# 1-Schematic_R4_Odzyskowa_Dolna.net
KiCad netlist of a schematic drawn in EasyEDA
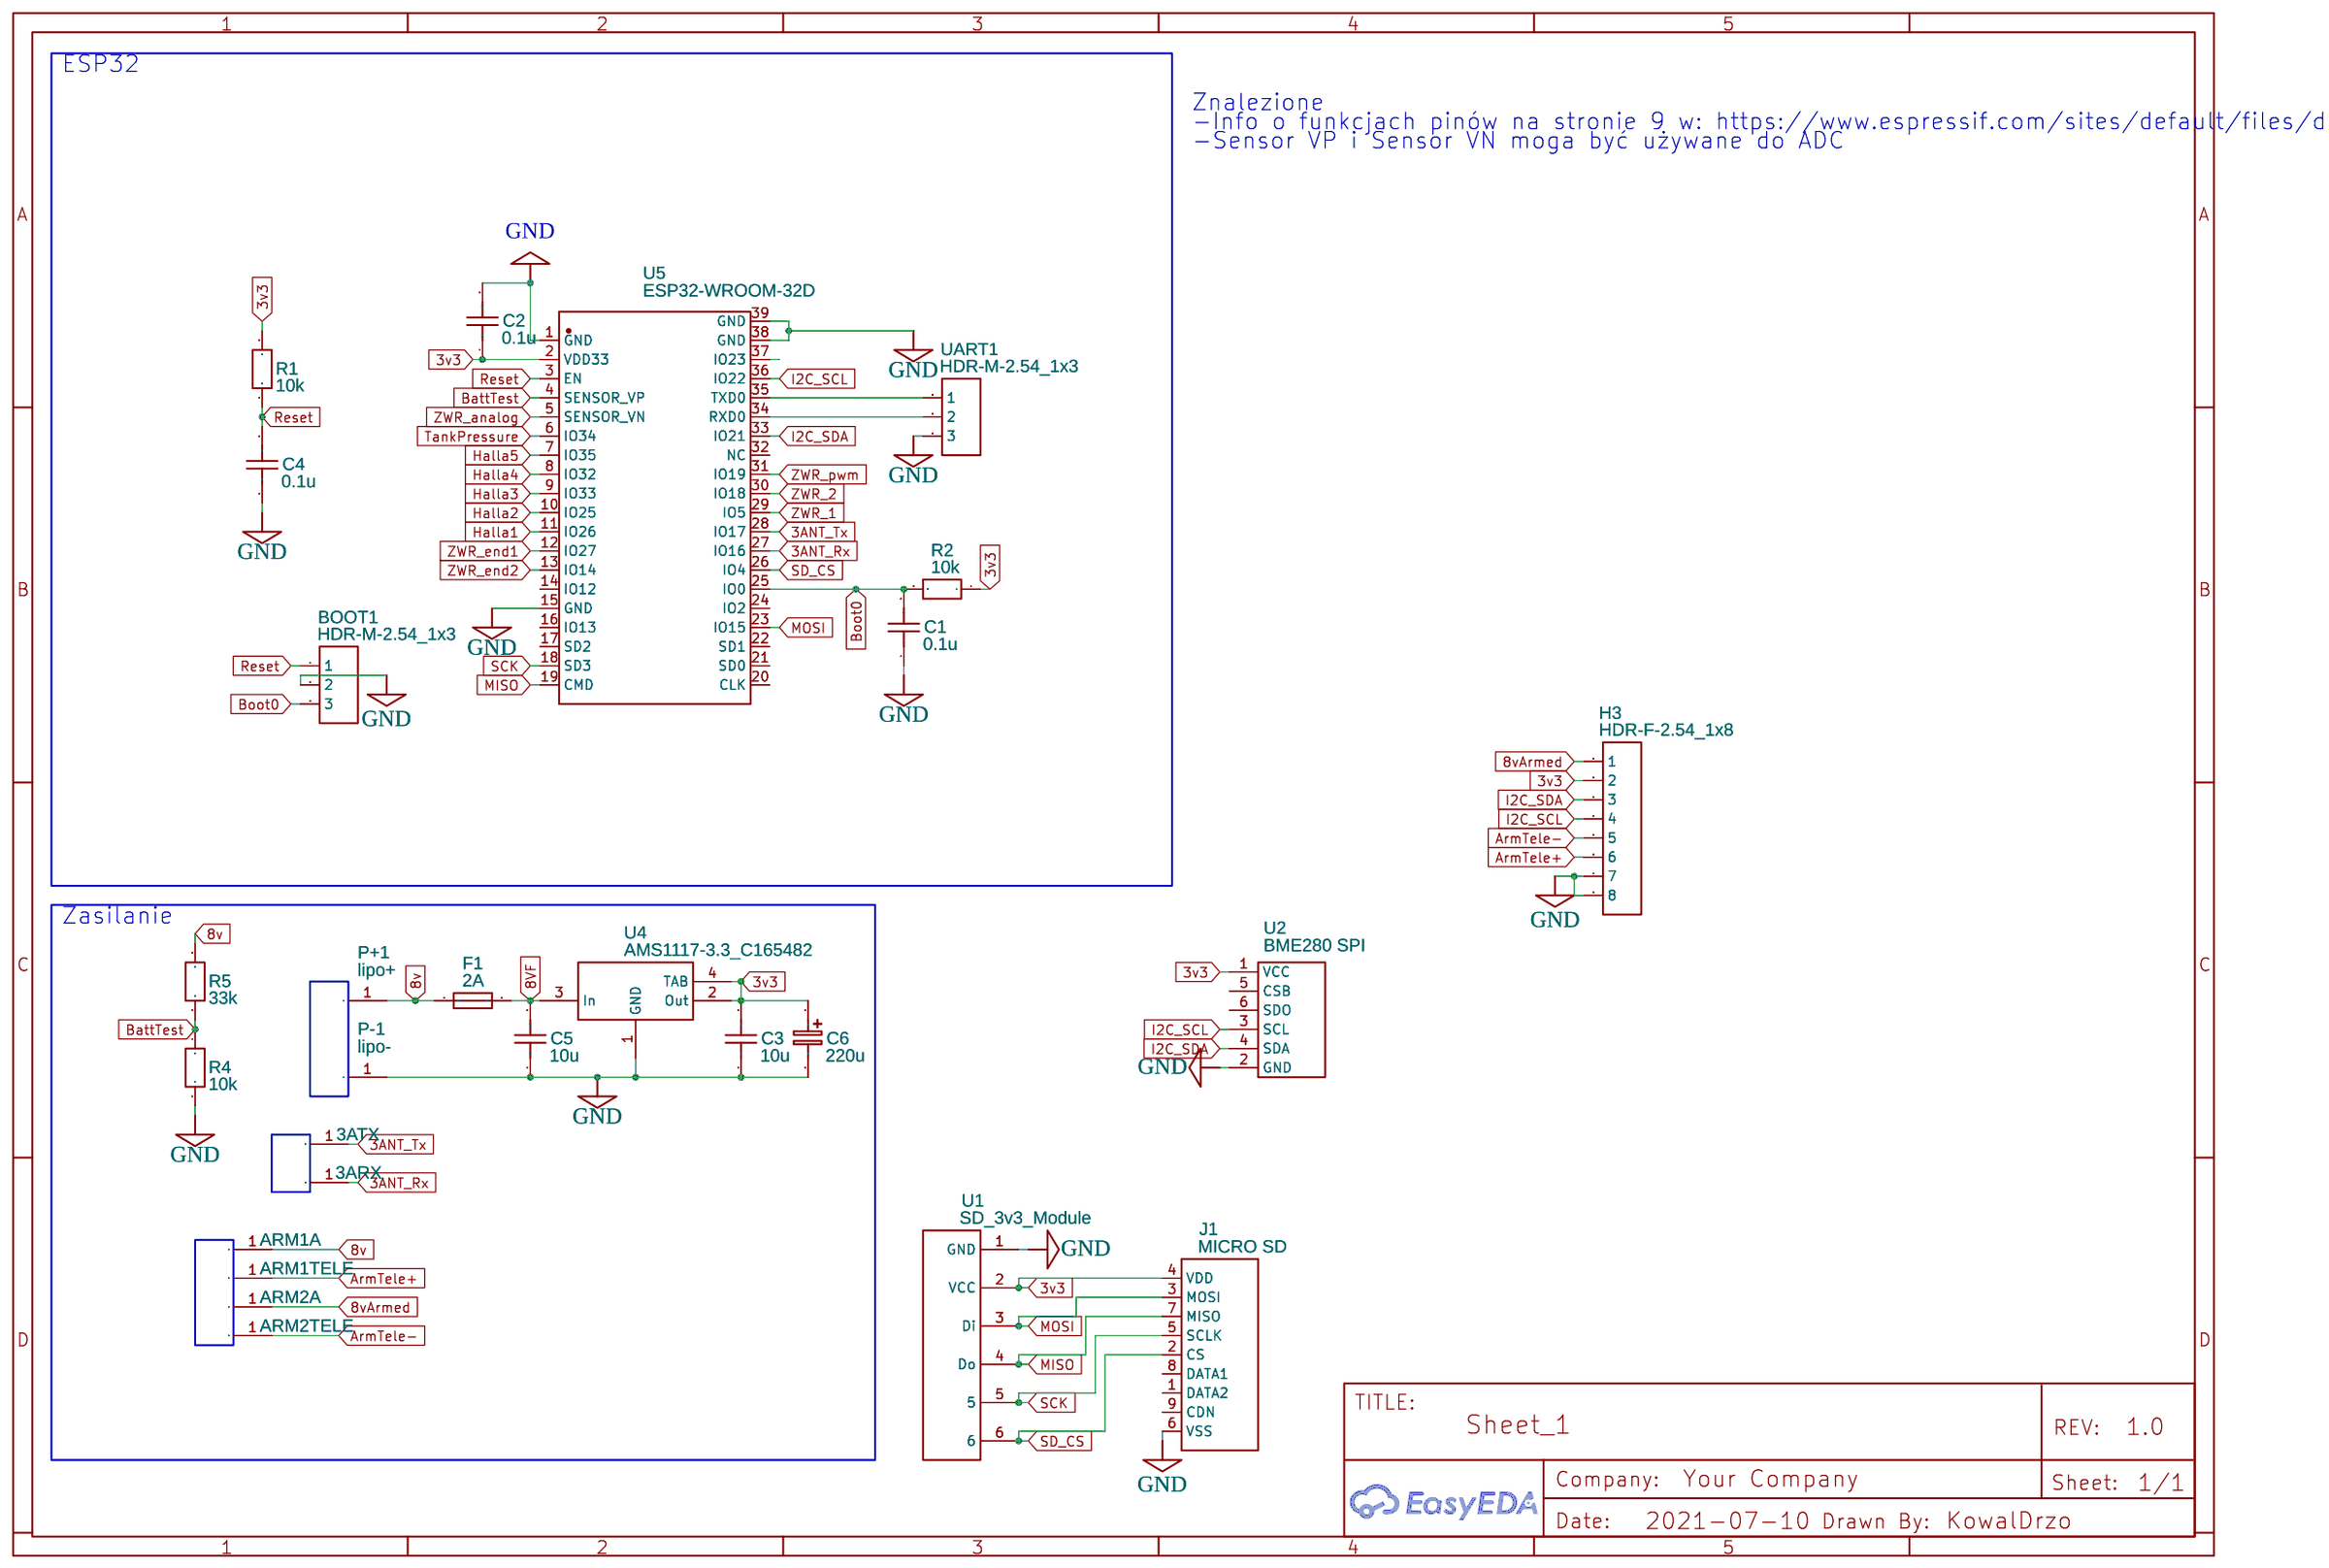
[diagram p0: ESP]
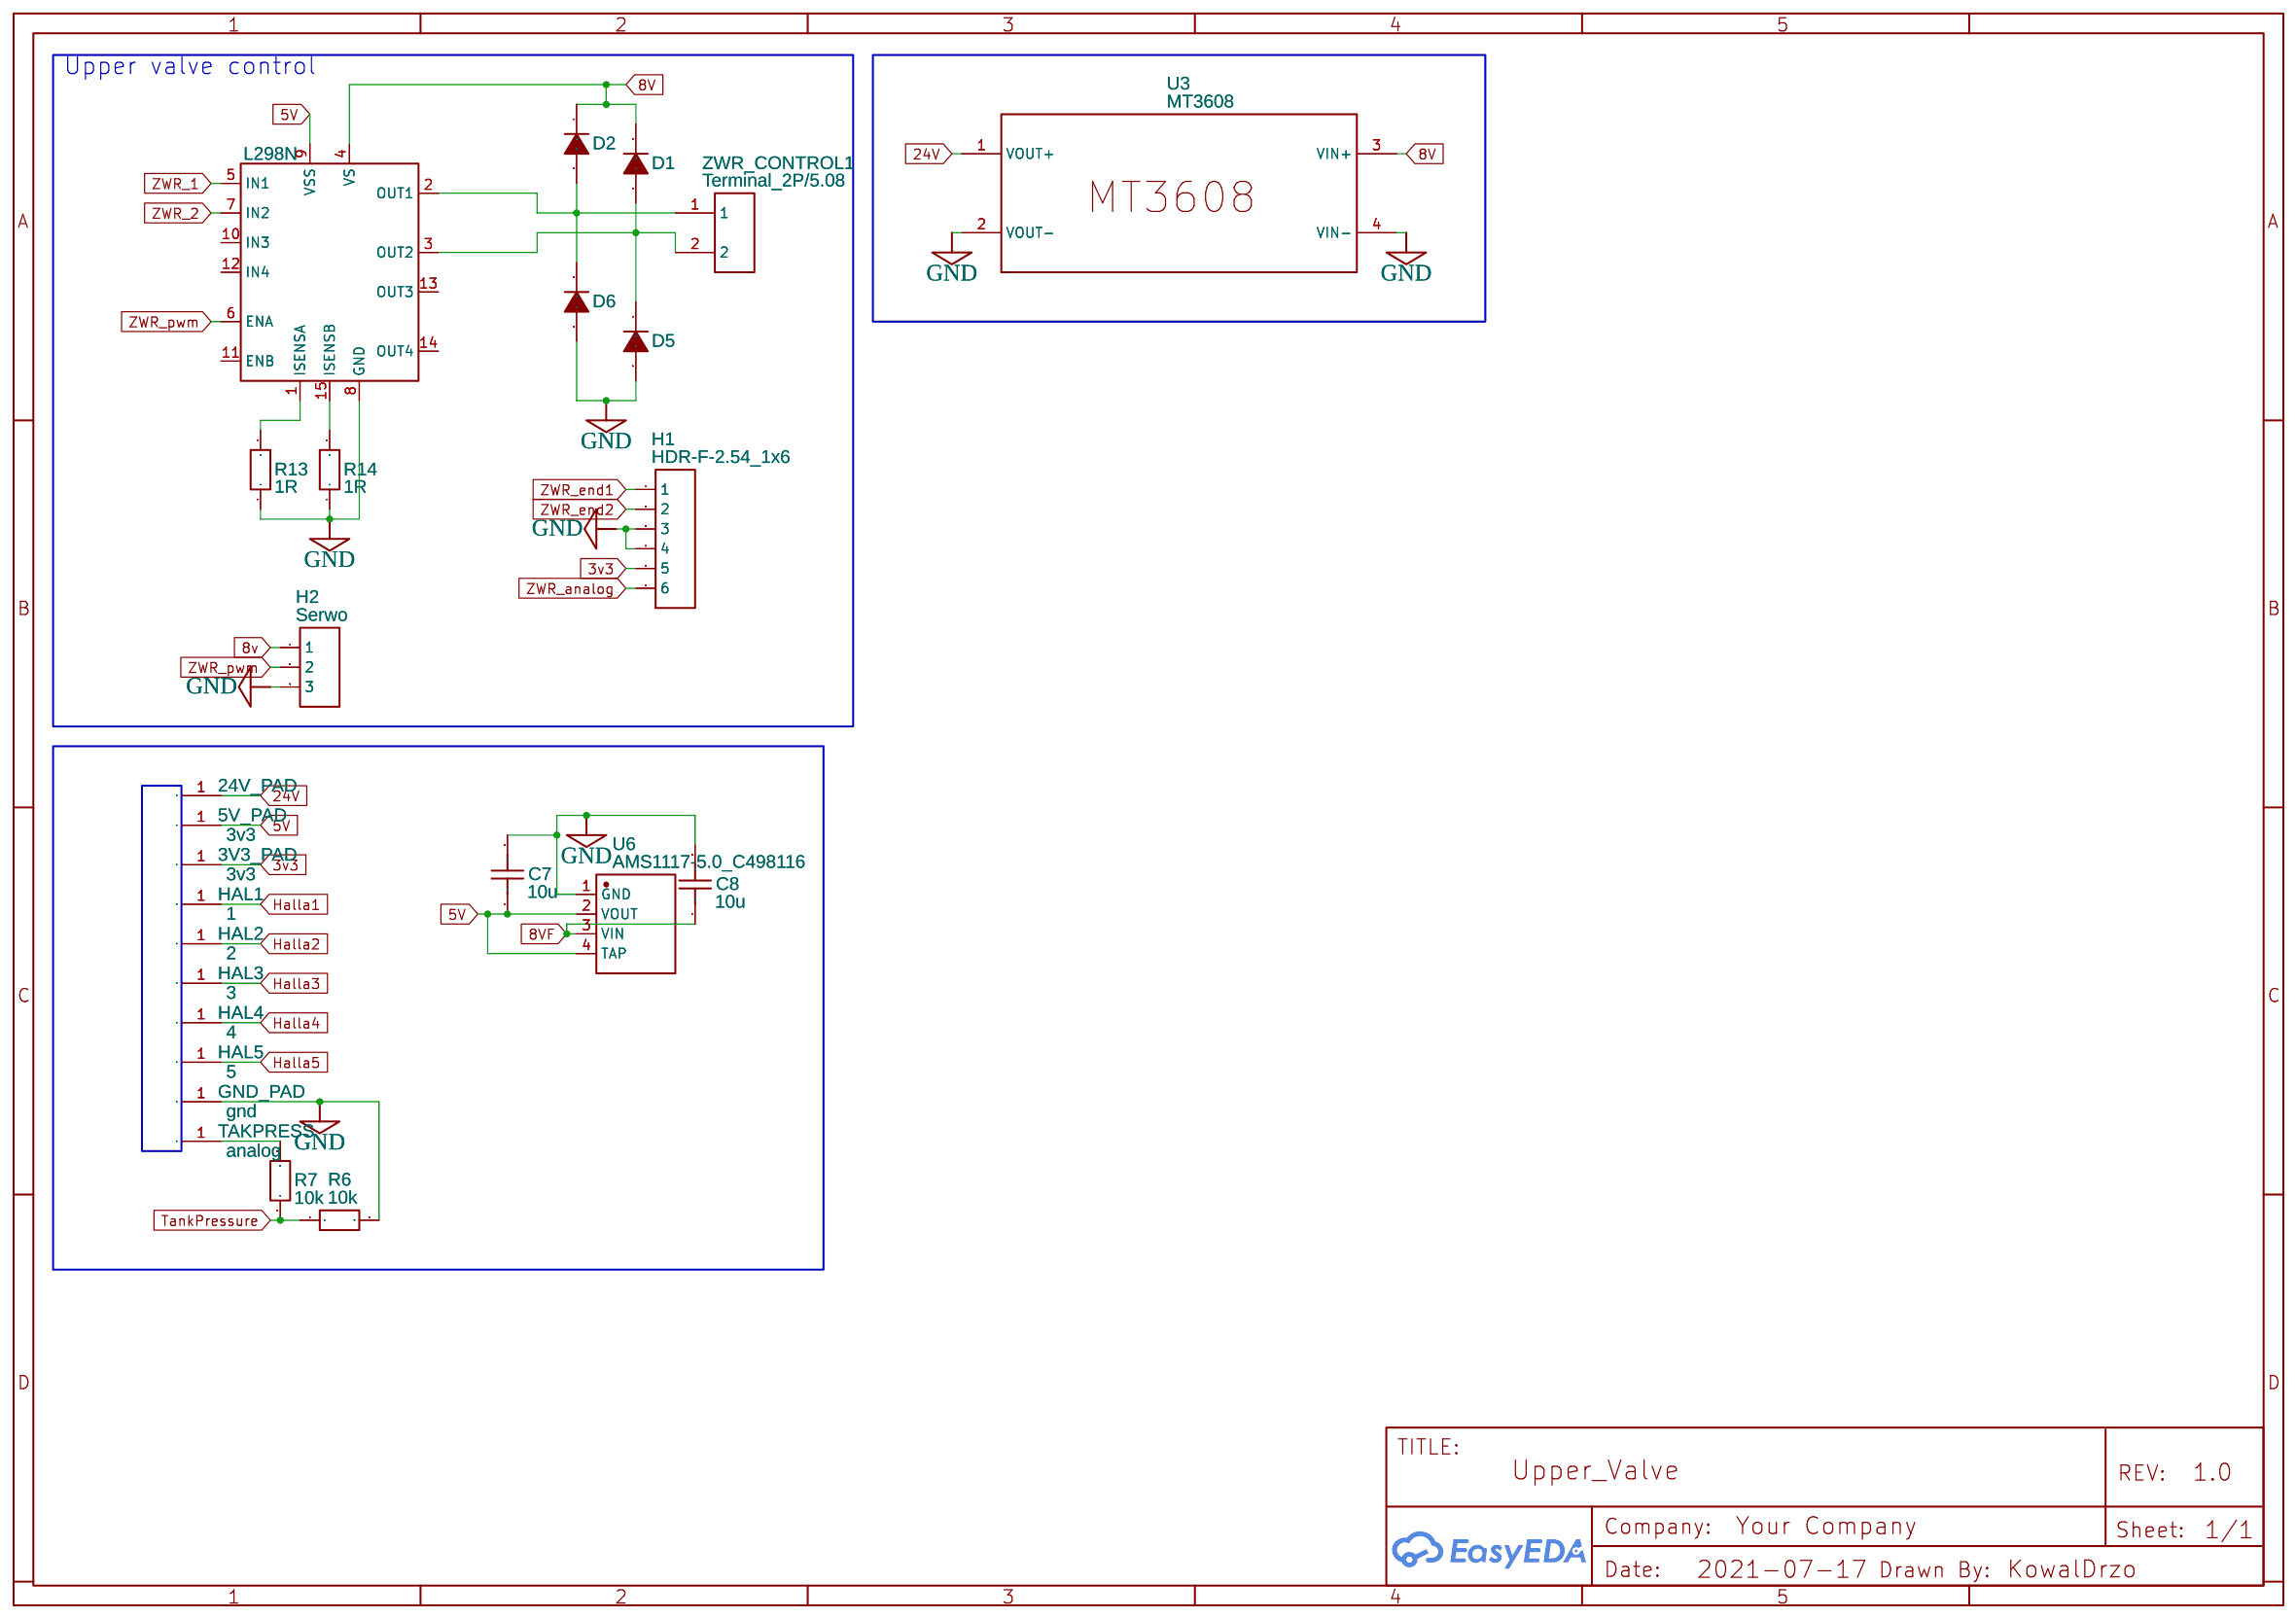
[diagram p1: Tank_control]

(export (version "E")
  (design (tool "Eeschema 10.0.6"))
  (components
    (comp (ref "3ARX") (value "3v3") (libsource (lib "") (part "pad 4mm_2")))
    (comp (ref "3ATX") (value "3v3") (libsource (lib "") (part "pad 4mm_5")))
    (comp (ref "ARM1A") (value "3v3") (libsource (lib "") (part "pad 4mm_3")))
    (comp (ref "ARM1TELE") (value "3v3") (libsource (lib "") (part "pad 4mm_4")))
    (comp (ref "ARM2A") (value "3v3") (libsource (lib "") (part "pad 4mm_1")))
    (comp (ref "ARM2TELE") (value "3v3") (libsource (lib "") (part "pad 4mm_6")))
    (comp (ref "BOOT1")
      (value "HDR-M-2.54_1x3")
      (fields (field (name "BOM_Supplier Part") "C180248"))
      (libsource (lib "") (part "HDR-M-2.54_1x3_1"))
    )
    (comp (ref "C1") (value "0.1u") (libsource (lib "") (part "C_0805_US")))
    (comp (ref "C2") (value "0.1u") (libsource (lib "") (part "C_0805_US")))
    (comp (ref "C3") (value "10u") (libsource (lib "") (part "C_0805_US")))
    (comp (ref "C4") (value "0.1u") (libsource (lib "") (part "C_0805_US")))
    (comp (ref "C5") (value "10u") (libsource (lib "") (part "C_0805_US")))
    (comp (ref "C6") (value "220u") (libsource (lib "") (part "CE_TH_D5.0×F2.0_EU")))
    (comp (ref "F1")
      (value "2A")
      (fields
        (field (name "BOM_Manufacturer Part") "0468002.NRHF")
        (field (name "BOM_Supplier Part") "C187611")
      )
      (libsource (lib "") (part "FUSE 1206"))
    )
    (comp (ref "H3")
      (value "HDR-F-2.54_1x8")
      (fields (field (name "BOM_Supplier Part") "C225505"))
      (libsource (lib "") (part "HDR-F-2.54_1x8"))
    )
    (comp (ref "J1")
      (value "MICRO SD")
      (fields (field (name "BOM_Manufacturer Part") "?"))
      (libsource (lib "") (part "MICRO SD"))
    )
    (comp (ref "P+1") (value "lipo+") (libsource (lib "") (part "pad 4mm")))
    (comp (ref "P-1") (value "lipo-") (libsource (lib "") (part "pad 4mm_7")))
    (comp (ref "R1") (value "10k") (libsource (lib "") (part "R_0805_EU_2")))
    (comp (ref "R2") (value "10k") (libsource (lib "") (part "R_0805_EU")))
    (comp (ref "R4") (value "10k") (libsource (lib "") (part "R_0805_EU_1")))
    (comp (ref "R5") (value "33k") (libsource (lib "") (part "R_0805_EU_2")))
    (comp (ref "U1") (value "SD_3v3_Module") (libsource (lib "") (part "SD_3v3_Module")))
    (comp (ref "U2")
      (value "BME280 SPI")
      (fields
        (field (name "BOM_Manufacturer Part") "GY-BME230-3.3 BreakoutNew SchematicLib")
        (field (name "BOM_Supplier Part") "undefined")
      )
      (libsource (lib "") (part "BME280 SPI"))
    )
    (comp (ref "U4")
      (value "AMS1117-3.3_C165482")
      (fields
        (field (name "BOM_Manufacturer Part") "AMS1117-3.3")
        (field (name "BOM_Supplier Part") "C165482")
      )
      (libsource (lib "") (part "AMS1117-3.3_C165482"))
    )
    (comp (ref "U5")
      (value "ESP32-WROOM-32D")
      (fields (field (name "BOM_Supplier Part") "C473012"))
      (libsource (lib "") (part "ESP32-WROOM-32D"))
    )
    (comp (ref "UART1")
      (value "HDR-M-2.54_1x3")
      (fields (field (name "BOM_Supplier Part") "C180248"))
      (libsource (lib "") (part "HDR-M-2.54_1x3"))
    )
    (comp (ref "3V3_PAD") (value "3v3") (libsource (lib "") (part "pad 4mm_2")))
    (comp (ref "5V_PAD") (value "3v3") (libsource (lib "") (part "pad 4mm_4")))
    (comp (ref "24V_PAD") (value "3v3") (libsource (lib "") (part "pad 4mm_1")))
    (comp (ref "C7") (value "10u") (libsource (lib "") (part "C_0805_US")))
    (comp (ref "C8") (value "10u") (libsource (lib "") (part "C_0805_US")))
    (comp (ref "D1")
      (value "US2G_C49263")
      (fields (field (name "BOM_Manufacturer Part") "US2G") (field (name "BOM_Supplier Part") "C49263"))
      (libsource (lib "") (part "US2G_C49263"))
    )
    (comp (ref "D2")
      (value "US2G_C49263")
      (fields (field (name "BOM_Manufacturer Part") "US2G") (field (name "BOM_Supplier Part") "C49263"))
      (libsource (lib "") (part "US2G_C49263"))
    )
    (comp (ref "D5")
      (value "US2G_C49263")
      (fields (field (name "BOM_Manufacturer Part") "US2G") (field (name "BOM_Supplier Part") "C49263"))
      (libsource (lib "") (part "US2G_C49263"))
    )
    (comp (ref "D6")
      (value "US2G_C49263")
      (fields (field (name "BOM_Manufacturer Part") "US2G") (field (name "BOM_Supplier Part") "C49263"))
      (libsource (lib "") (part "US2G_C49263"))
    )
    (comp (ref "GND_PAD") (value "gnd") (libsource (lib "") (part "pad 4mm_3")))
    (comp (ref "H1")
      (value "HDR-F-2.54_1x6")
      (fields (field (name "BOM_Supplier Part") "C40877"))
      (libsource (lib "") (part "HDR-F-2.54_1x6"))
    )
    (comp (ref "H2")
      (value "Serwo")
      (fields (field (name "BOM_Supplier Part") "C146690"))
      (libsource (lib "") (part "HDR-F-2.54_1x3"))
    )
    (comp (ref "HAL1") (value "1") (libsource (lib "") (part "pad 4mm_5")))
    (comp (ref "HAL2") (value "2") (libsource (lib "") (part "pad 4mm_5")))
    (comp (ref "HAL3") (value "3") (libsource (lib "") (part "pad 4mm_5")))
    (comp (ref "HAL4") (value "4") (libsource (lib "") (part "pad 4mm_5")))
    (comp (ref "HAL5") (value "5") (libsource (lib "") (part "pad 4mm_5")))
    (comp (ref "MOD3")
      (value "L298N")
      (fields (field (name "BOM_Supplier Part") "C19922"))
      (libsource (lib "") (part "L298N"))
    )
    (comp (ref "R6") (value "10k") (libsource (lib "") (part "R_0805_EU")))
    (comp (ref "R7") (value "10k") (libsource (lib "") (part "R_0805_EU_1")))
    (comp (ref "R13") (value "1R") (libsource (lib "") (part "R_1206_EU")))
    (comp (ref "R14") (value "1R") (libsource (lib "") (part "R_1206_EU")))
    (comp (ref "TAKPRESS") (value "analog") (libsource (lib "") (part "pad 4mm")))
    (comp (ref "U3")
      (value "MT3608")
      (fields (field (name "BOM_Manufacturer Part") "New SchematicLib"))
      (libsource (lib "") (part "MT3608"))
    )
    (comp (ref "U6")
      (value "AMS1117-5.0_C498116")
      (fields
        (field (name "BOM_Manufacturer Part") "AMS1117-5.0")
        (field (name "BOM_Supplier Part") "C498116")
      )
      (libsource (lib "") (part "AMS1117-5.0_C498116"))
    )
    (comp (ref "ZWR_CONTROL1")
      (value "Terminal_2P/5.08")
      (fields (field (name "BOM_Manufacturer Part") "Screw terminal 2p"))
      (libsource (lib "") (part "Terminal_2P/5.08"))
    )
  )
  (nets
    (net (code "1") (name "3ANT_Rx") (class "Default")
      (node (ref "3ARX") (pin "1") (pinfunction "1_1") (pintype "unspecified"))
      (node (ref "U5") (pin "27") (pinfunction "IO16_27") (pintype "unspecified"))
    )
    (net (code "2") (name "3ANT_Tx") (class "Default")
      (node (ref "3ATX") (pin "1") (pinfunction "1_1") (pintype "unspecified"))
      (node (ref "U5") (pin "28") (pinfunction "IO17_28") (pintype "unspecified"))
    )
    (net (code "3") (name "3v3") (class "Default")
      (node (ref "3V3_PAD") (pin "1") (pinfunction "1_1") (pintype "unspecified"))
      (node (ref "C2") (pin "1") (pinfunction "1_1") (pintype "unspecified"))
      (node (ref "C3") (pin "2") (pinfunction "2_2") (pintype "unspecified"))
      (node (ref "C6") (pin "1") (pinfunction "1_1") (pintype "unspecified"))
      (node (ref "H1") (pin "5") (pinfunction "5_5") (pintype "input"))
      (node (ref "H3") (pin "2") (pinfunction "2_2") (pintype "unspecified"))
      (node (ref "J1") (pin "4") (pinfunction "VDD_4") (pintype "unspecified"))
      (node (ref "R1") (pin "2") (pinfunction "2_2") (pintype "unspecified"))
      (node (ref "R2") (pin "1") (pinfunction "1_1") (pintype "unspecified"))
      (node (ref "U1") (pin "2") (pinfunction "VCC_2") (pintype "unspecified"))
      (node (ref "U2") (pin "1") (pinfunction "VCC_1") (pintype "unspecified"))
      (node (ref "U4") (pin "2") (pinfunction "Out_2") (pintype "unspecified"))
      (node (ref "U4") (pin "4") (pinfunction "TAB_4") (pintype "unspecified"))
      (node (ref "U5") (pin "2") (pinfunction "VDD33_2") (pintype "unspecified"))
    )
    (net (code "4") (name "5V") (class "Default")
      (node (ref "5V_PAD") (pin "1") (pinfunction "1_1") (pintype "unspecified"))
      (node (ref "C7") (pin "1") (pinfunction "1_1") (pintype "unspecified"))
      (node (ref "MOD3") (pin "9") (pinfunction "VSS_9") (pintype "unspecified"))
      (node (ref "U6") (pin "2") (pinfunction "VOUT_2") (pintype "unspecified"))
      (node (ref "U6") (pin "4") (pinfunction "TAP_4") (pintype "unspecified"))
    )
    (net (code "5") (name "8V") (class "Default")
      (node (ref "D1") (pin "1") (pinfunction "K_1") (pintype "unspecified"))
      (node (ref "D2") (pin "1") (pinfunction "K_1") (pintype "unspecified"))
      (node (ref "MOD3") (pin "4") (pinfunction "VS_4") (pintype "unspecified"))
      (node (ref "U3") (pin "3") (pinfunction "VIN+_3") (pintype "unspecified"))
    )
    (net (code "6") (name "8VF") (class "Default")
      (node (ref "C5") (pin "2") (pinfunction "2_2") (pintype "unspecified"))
      (node (ref "C8") (pin "1") (pinfunction "1_1") (pintype "unspecified"))
      (node (ref "F1") (pin "2") (pinfunction "2_2") (pintype "unspecified"))
      (node (ref "U4") (pin "3") (pinfunction "In_3") (pintype "unspecified"))
      (node (ref "U6") (pin "3") (pinfunction "VIN_3") (pintype "unspecified"))
    )
    (net (code "7") (name "8v") (class "Default")
      (node (ref "ARM1A") (pin "1") (pinfunction "1_1") (pintype "unspecified"))
      (node (ref "F1") (pin "1") (pinfunction "1_1") (pintype "unspecified"))
      (node (ref "H2") (pin "1") (pinfunction "1_1") (pintype "input"))
      (node (ref "P+1") (pin "1") (pinfunction "1_1") (pintype "unspecified"))
      (node (ref "R5") (pin "2") (pinfunction "2_2") (pintype "unspecified"))
    )
    (net (code "8") (name "8vArmed") (class "Default")
      (node (ref "ARM2A") (pin "1") (pinfunction "1_1") (pintype "unspecified"))
      (node (ref "H3") (pin "1") (pinfunction "1_1") (pintype "unspecified"))
    )
    (net (code "9") (name "24V") (class "Default")
      (node (ref "24V_PAD") (pin "1") (pinfunction "1_1") (pintype "unspecified"))
      (node (ref "U3") (pin "1") (pinfunction "VOUT+_1") (pintype "unspecified"))
    )
    (net (code "10") (name "ArmTele+") (class "Default")
      (node (ref "ARM1TELE") (pin "1") (pinfunction "1_1") (pintype "unspecified"))
      (node (ref "H3") (pin "6") (pinfunction "6_6") (pintype "unspecified"))
    )
    (net (code "11") (name "ArmTele-") (class "Default")
      (node (ref "ARM2TELE") (pin "1") (pinfunction "1_1") (pintype "unspecified"))
      (node (ref "H3") (pin "5") (pinfunction "5_5") (pintype "unspecified"))
    )
    (net (code "12") (name "BattTest") (class "Default")
      (node (ref "R4") (pin "1") (pinfunction "1_1") (pintype "unspecified"))
      (node (ref "R5") (pin "1") (pinfunction "1_1") (pintype "unspecified"))
      (node (ref "U5") (pin "4") (pinfunction "SENSOR_VP_4") (pintype "unspecified"))
    )
    (net (code "13") (name "Boot0") (class "Default")
      (node (ref "BOOT1") (pin "3") (pinfunction "3_3") (pintype "input"))
      (node (ref "C1") (pin "2") (pinfunction "2_2") (pintype "unspecified"))
      (node (ref "R2") (pin "2") (pinfunction "2_2") (pintype "unspecified"))
      (node (ref "U5") (pin "25") (pinfunction "IO0_25") (pintype "unspecified"))
    )
    (net (code "14") (name "GND") (class "Default")
      (node (ref "BOOT1") (pin "2") (pinfunction "2_2") (pintype "input"))
      (node (ref "C1") (pin "1") (pinfunction "1_1") (pintype "unspecified"))
      (node (ref "C2") (pin "2") (pinfunction "2_2") (pintype "unspecified"))
      (node (ref "C3") (pin "1") (pinfunction "1_1") (pintype "unspecified"))
      (node (ref "C4") (pin "1") (pinfunction "1_1") (pintype "unspecified"))
      (node (ref "C5") (pin "1") (pinfunction "1_1") (pintype "unspecified"))
      (node (ref "C6") (pin "2") (pinfunction "2_2") (pintype "unspecified"))
      (node (ref "C7") (pin "2") (pinfunction "2_2") (pintype "unspecified"))
      (node (ref "C8") (pin "2") (pinfunction "2_2") (pintype "unspecified"))
      (node (ref "D5") (pin "2") (pinfunction "A_2") (pintype "unspecified"))
      (node (ref "D6") (pin "2") (pinfunction "A_2") (pintype "unspecified"))
      (node (ref "GND_PAD") (pin "1") (pinfunction "1_1") (pintype "unspecified"))
      (node (ref "H1") (pin "3") (pinfunction "3_3") (pintype "input"))
      (node (ref "H1") (pin "4") (pinfunction "4_4") (pintype "input"))
      (node (ref "H2") (pin "3") (pinfunction "3_3") (pintype "input"))
      (node (ref "H3") (pin "7") (pinfunction "7_7") (pintype "unspecified"))
      (node (ref "H3") (pin "8") (pinfunction "8_8") (pintype "unspecified"))
      (node (ref "J1") (pin "6") (pinfunction "VSS_6") (pintype "unspecified"))
      (node (ref "MOD3") (pin "8") (pinfunction "GND_8") (pintype "unspecified"))
      (node (ref "P-1") (pin "1") (pinfunction "1_1") (pintype "unspecified"))
      (node (ref "R13") (pin "1") (pinfunction "1_1") (pintype "unspecified"))
      (node (ref "R14") (pin "1") (pinfunction "1_1") (pintype "unspecified"))
      (node (ref "R4") (pin "2") (pinfunction "2_2") (pintype "unspecified"))
      (node (ref "R6") (pin "2") (pinfunction "2_2") (pintype "unspecified"))
      (node (ref "U1") (pin "1") (pinfunction "GND_1") (pintype "unspecified"))
      (node (ref "U2") (pin "2") (pinfunction "GND_2") (pintype "unspecified"))
      (node (ref "U3") (pin "2") (pinfunction "VOUT-_2") (pintype "unspecified"))
      (node (ref "U3") (pin "4") (pinfunction "VIN-_4") (pintype "unspecified"))
      (node (ref "U4") (pin "1") (pinfunction "GND_1") (pintype "unspecified"))
      (node (ref "U5") (pin "1") (pinfunction "GND_1") (pintype "unspecified"))
      (node (ref "U5") (pin "15") (pinfunction "GND_15") (pintype "unspecified"))
      (node (ref "U5") (pin "38") (pinfunction "GND_38") (pintype "unspecified"))
      (node (ref "U5") (pin "39") (pinfunction "GND_39") (pintype "unspecified"))
      (node (ref "U6") (pin "1") (pinfunction "GND_1") (pintype "unspecified"))
      (node (ref "UART1") (pin "3") (pinfunction "3_3") (pintype "input"))
    )
    (net (code "15") (name "Halla1") (class "Default")
      (node (ref "HAL1") (pin "1") (pinfunction "1_1") (pintype "unspecified"))
      (node (ref "U5") (pin "11") (pinfunction "IO26_11") (pintype "unspecified"))
    )
    (net (code "16") (name "Halla2") (class "Default")
      (node (ref "HAL2") (pin "1") (pinfunction "1_1") (pintype "unspecified"))
      (node (ref "U5") (pin "10") (pinfunction "IO25_10") (pintype "unspecified"))
    )
    (net (code "17") (name "Halla3") (class "Default")
      (node (ref "HAL3") (pin "1") (pinfunction "1_1") (pintype "unspecified"))
      (node (ref "U5") (pin "9") (pinfunction "IO33_9") (pintype "unspecified"))
    )
    (net (code "18") (name "Halla4") (class "Default")
      (node (ref "HAL4") (pin "1") (pinfunction "1_1") (pintype "unspecified"))
      (node (ref "U5") (pin "8") (pinfunction "IO32_8") (pintype "unspecified"))
    )
    (net (code "19") (name "Halla5") (class "Default")
      (node (ref "HAL5") (pin "1") (pinfunction "1_1") (pintype "unspecified"))
      (node (ref "U5") (pin "7") (pinfunction "IO35_7") (pintype "unspecified"))
    )
    (net (code "20") (name "I2C_SCL") (class "Default")
      (node (ref "H3") (pin "4") (pinfunction "4_4") (pintype "unspecified"))
      (node (ref "U2") (pin "3") (pinfunction "SCL_3") (pintype "unspecified"))
      (node (ref "U5") (pin "36") (pinfunction "IO22_36") (pintype "unspecified"))
    )
    (net (code "21") (name "I2C_SDA") (class "Default")
      (node (ref "H3") (pin "3") (pinfunction "3_3") (pintype "unspecified"))
      (node (ref "U2") (pin "4") (pinfunction "SDA_4") (pintype "unspecified"))
      (node (ref "U5") (pin "33") (pinfunction "IO21_33") (pintype "unspecified"))
    )
    (net (code "22") (name "MISO") (class "Default")
      (node (ref "J1") (pin "7") (pinfunction "MISO_7") (pintype "unspecified"))
      (node (ref "U1") (pin "4") (pinfunction "Do_4") (pintype "unspecified"))
      (node (ref "U5") (pin "19") (pinfunction "CMD_19") (pintype "unspecified"))
    )
    (net (code "23") (name "MOSI") (class "Default")
      (node (ref "J1") (pin "3") (pinfunction "MOSI_3") (pintype "unspecified"))
      (node (ref "U1") (pin "3") (pinfunction "Di_3") (pintype "unspecified"))
      (node (ref "U5") (pin "23") (pinfunction "IO15_23") (pintype "unspecified"))
    )
    (net (code "24") (name "Net-(D1-A)") (class "Default")
      (node (ref "D1") (pin "2") (pinfunction "A_2") (pintype "unspecified"))
      (node (ref "D5") (pin "1") (pinfunction "K_1") (pintype "unspecified"))
      (node (ref "MOD3") (pin "3") (pinfunction "OUT2_3") (pintype "unspecified"))
      (node (ref "ZWR_CONTROL1") (pin "2") (pinfunction "2_2") (pintype "unspecified"))
    )
    (net (code "25") (name "Net-(D2-A)") (class "Default")
      (node (ref "D2") (pin "2") (pinfunction "A_2") (pintype "unspecified"))
      (node (ref "D6") (pin "1") (pinfunction "K_1") (pintype "unspecified"))
      (node (ref "MOD3") (pin "2") (pinfunction "OUT1_2") (pintype "unspecified"))
      (node (ref "ZWR_CONTROL1") (pin "1") (pinfunction "1_1") (pintype "unspecified"))
    )
    (net (code "26") (name "Net-(MOD3-ISENSA)") (class "Default")
      (node (ref "MOD3") (pin "1") (pinfunction "ISENSA_1") (pintype "unspecified"))
      (node (ref "R13") (pin "2") (pinfunction "2_2") (pintype "unspecified"))
    )
    (net (code "27") (name "Net-(MOD3-ISENSB)") (class "Default")
      (node (ref "MOD3") (pin "15") (pinfunction "ISENSB_15") (pintype "unspecified"))
      (node (ref "R14") (pin "2") (pinfunction "2_2") (pintype "unspecified"))
    )
    (net (code "28") (name "Net-(R7-Pad2)") (class "Default")
      (node (ref "R7") (pin "2") (pinfunction "2_2") (pintype "unspecified"))
      (node (ref "TAKPRESS") (pin "1") (pinfunction "1_1") (pintype "unspecified"))
    )
    (net (code "29") (name "Net-(U5-RXD0)") (class "Default")
      (node (ref "U5") (pin "34") (pinfunction "RXD0_34") (pintype "unspecified"))
      (node (ref "UART1") (pin "2") (pinfunction "2_2") (pintype "input"))
    )
    (net (code "30") (name "Net-(U5-TXD0)") (class "Default")
      (node (ref "U5") (pin "35") (pinfunction "TXD0_35") (pintype "unspecified"))
      (node (ref "UART1") (pin "1") (pinfunction "1_1") (pintype "input"))
    )
    (net (code "31") (name "Reset") (class "Default")
      (node (ref "BOOT1") (pin "1") (pinfunction "1_1") (pintype "input"))
      (node (ref "C4") (pin "2") (pinfunction "2_2") (pintype "unspecified"))
      (node (ref "R1") (pin "1") (pinfunction "1_1") (pintype "unspecified"))
      (node (ref "U5") (pin "3") (pinfunction "EN_3") (pintype "unspecified"))
    )
    (net (code "32") (name "SCK") (class "Default")
      (node (ref "J1") (pin "5") (pinfunction "SCLK_5") (pintype "unspecified"))
      (node (ref "U1") (pin "5") (pinfunction "5_5") (pintype "unspecified"))
      (node (ref "U5") (pin "18") (pinfunction "SD3_18") (pintype "unspecified"))
    )
    (net (code "33") (name "SD_CS") (class "Default")
      (node (ref "J1") (pin "2") (pinfunction "CS_2") (pintype "unspecified"))
      (node (ref "U1") (pin "6") (pinfunction "6_6") (pintype "unspecified"))
      (node (ref "U5") (pin "26") (pinfunction "IO4_26") (pintype "unspecified"))
    )
    (net (code "34") (name "TankPressure") (class "Default")
      (node (ref "R6") (pin "1") (pinfunction "1_1") (pintype "unspecified"))
      (node (ref "R7") (pin "1") (pinfunction "1_1") (pintype "unspecified"))
      (node (ref "U5") (pin "6") (pinfunction "IO34_6") (pintype "unspecified"))
    )
    (net (code "35") (name "ZWR_1") (class "Default")
      (node (ref "MOD3") (pin "5") (pinfunction "IN1_5") (pintype "unspecified"))
      (node (ref "U5") (pin "29") (pinfunction "IO5_29") (pintype "unspecified"))
    )
    (net (code "36") (name "ZWR_2") (class "Default")
      (node (ref "MOD3") (pin "7") (pinfunction "IN2_7") (pintype "unspecified"))
      (node (ref "U5") (pin "30") (pinfunction "IO18_30") (pintype "unspecified"))
    )
    (net (code "37") (name "ZWR_analog") (class "Default")
      (node (ref "H1") (pin "6") (pinfunction "6_6") (pintype "input"))
      (node (ref "U5") (pin "5") (pinfunction "SENSOR_VN_5") (pintype "unspecified"))
    )
    (net (code "38") (name "ZWR_end1") (class "Default")
      (node (ref "H1") (pin "1") (pinfunction "1_1") (pintype "input"))
      (node (ref "U5") (pin "12") (pinfunction "IO27_12") (pintype "unspecified"))
    )
    (net (code "39") (name "ZWR_end2") (class "Default")
      (node (ref "H1") (pin "2") (pinfunction "2_2") (pintype "input"))
      (node (ref "U5") (pin "13") (pinfunction "IO14_13") (pintype "unspecified"))
    )
    (net (code "40") (name "ZWR_pwm") (class "Default")
      (node (ref "H2") (pin "2") (pinfunction "2_2") (pintype "input"))
      (node (ref "MOD3") (pin "6") (pinfunction "ENA_6") (pintype "unspecified"))
      (node (ref "U5") (pin "31") (pinfunction "IO19_31") (pintype "unspecified"))
    )
    (net (code "41") (name "unconnected-(J1-CDN-Pad9)") (class "Default")
      (node (ref "J1") (pin "9") (pinfunction "CDN_9") (pintype "unspecified"))
    )
    (net (code "42") (name "unconnected-(J1-DATA1-Pad8)") (class "Default")
      (node (ref "J1") (pin "8") (pinfunction "DATA1_8") (pintype "unspecified"))
    )
    (net (code "43") (name "unconnected-(J1-DATA2-Pad1)") (class "Default")
      (node (ref "J1") (pin "1") (pinfunction "DATA2_1") (pintype "unspecified"))
    )
    (net (code "44") (name "unconnected-(MOD3-ENB-Pad11)") (class "Default")
      (node (ref "MOD3") (pin "11") (pinfunction "ENB_11") (pintype "unspecified"))
    )
    (net (code "45") (name "unconnected-(MOD3-IN3-Pad10)") (class "Default")
      (node (ref "MOD3") (pin "10") (pinfunction "IN3_10") (pintype "unspecified"))
    )
    (net (code "46") (name "unconnected-(MOD3-IN4-Pad12)") (class "Default")
      (node (ref "MOD3") (pin "12") (pinfunction "IN4_12") (pintype "unspecified"))
    )
    (net (code "47") (name "unconnected-(MOD3-OUT3-Pad13)") (class "Default")
      (node (ref "MOD3") (pin "13") (pinfunction "OUT3_13") (pintype "unspecified"))
    )
    (net (code "48") (name "unconnected-(MOD3-OUT4-Pad14)") (class "Default")
      (node (ref "MOD3") (pin "14") (pinfunction "OUT4_14") (pintype "unspecified"))
    )
    (net (code "49") (name "unconnected-(U2-CSB-Pad5)") (class "Default")
      (node (ref "U2") (pin "5") (pinfunction "CSB_5") (pintype "unspecified"))
    )
    (net (code "50") (name "unconnected-(U2-SDO-Pad6)") (class "Default")
      (node (ref "U2") (pin "6") (pinfunction "SDO_6") (pintype "unspecified"))
    )
    (net (code "51") (name "unconnected-(U5-CLK-Pad20)") (class "Default")
      (node (ref "U5") (pin "20") (pinfunction "CLK_20") (pintype "unspecified"))
    )
    (net (code "52") (name "unconnected-(U5-IO2-Pad24)") (class "Default")
      (node (ref "U5") (pin "24") (pinfunction "IO2_24") (pintype "unspecified"))
    )
    (net (code "53") (name "unconnected-(U5-IO12-Pad14)") (class "Default")
      (node (ref "U5") (pin "14") (pinfunction "IO12_14") (pintype "unspecified"))
    )
    (net (code "54") (name "unconnected-(U5-IO13-Pad16)") (class "Default")
      (node (ref "U5") (pin "16") (pinfunction "IO13_16") (pintype "unspecified"))
    )
    (net (code "55") (name "unconnected-(U5-IO23-Pad37)") (class "Default")
      (node (ref "U5") (pin "37") (pinfunction "IO23_37") (pintype "unspecified"))
    )
    (net (code "56") (name "unconnected-(U5-NC-Pad32)") (class "Default")
      (node (ref "U5") (pin "32") (pinfunction "NC_32") (pintype "unspecified"))
    )
    (net (code "57") (name "unconnected-(U5-SD0-Pad21)") (class "Default")
      (node (ref "U5") (pin "21") (pinfunction "SD0_21") (pintype "unspecified"))
    )
    (net (code "58") (name "unconnected-(U5-SD1-Pad22)") (class "Default")
      (node (ref "U5") (pin "22") (pinfunction "SD1_22") (pintype "unspecified"))
    )
    (net (code "59") (name "unconnected-(U5-SD2-Pad17)") (class "Default")
      (node (ref "U5") (pin "17") (pinfunction "SD2_17") (pintype "unspecified"))
    )
  )
)
